# 002-main.net
KiCad netlist of a schematic drawn in EAGLE
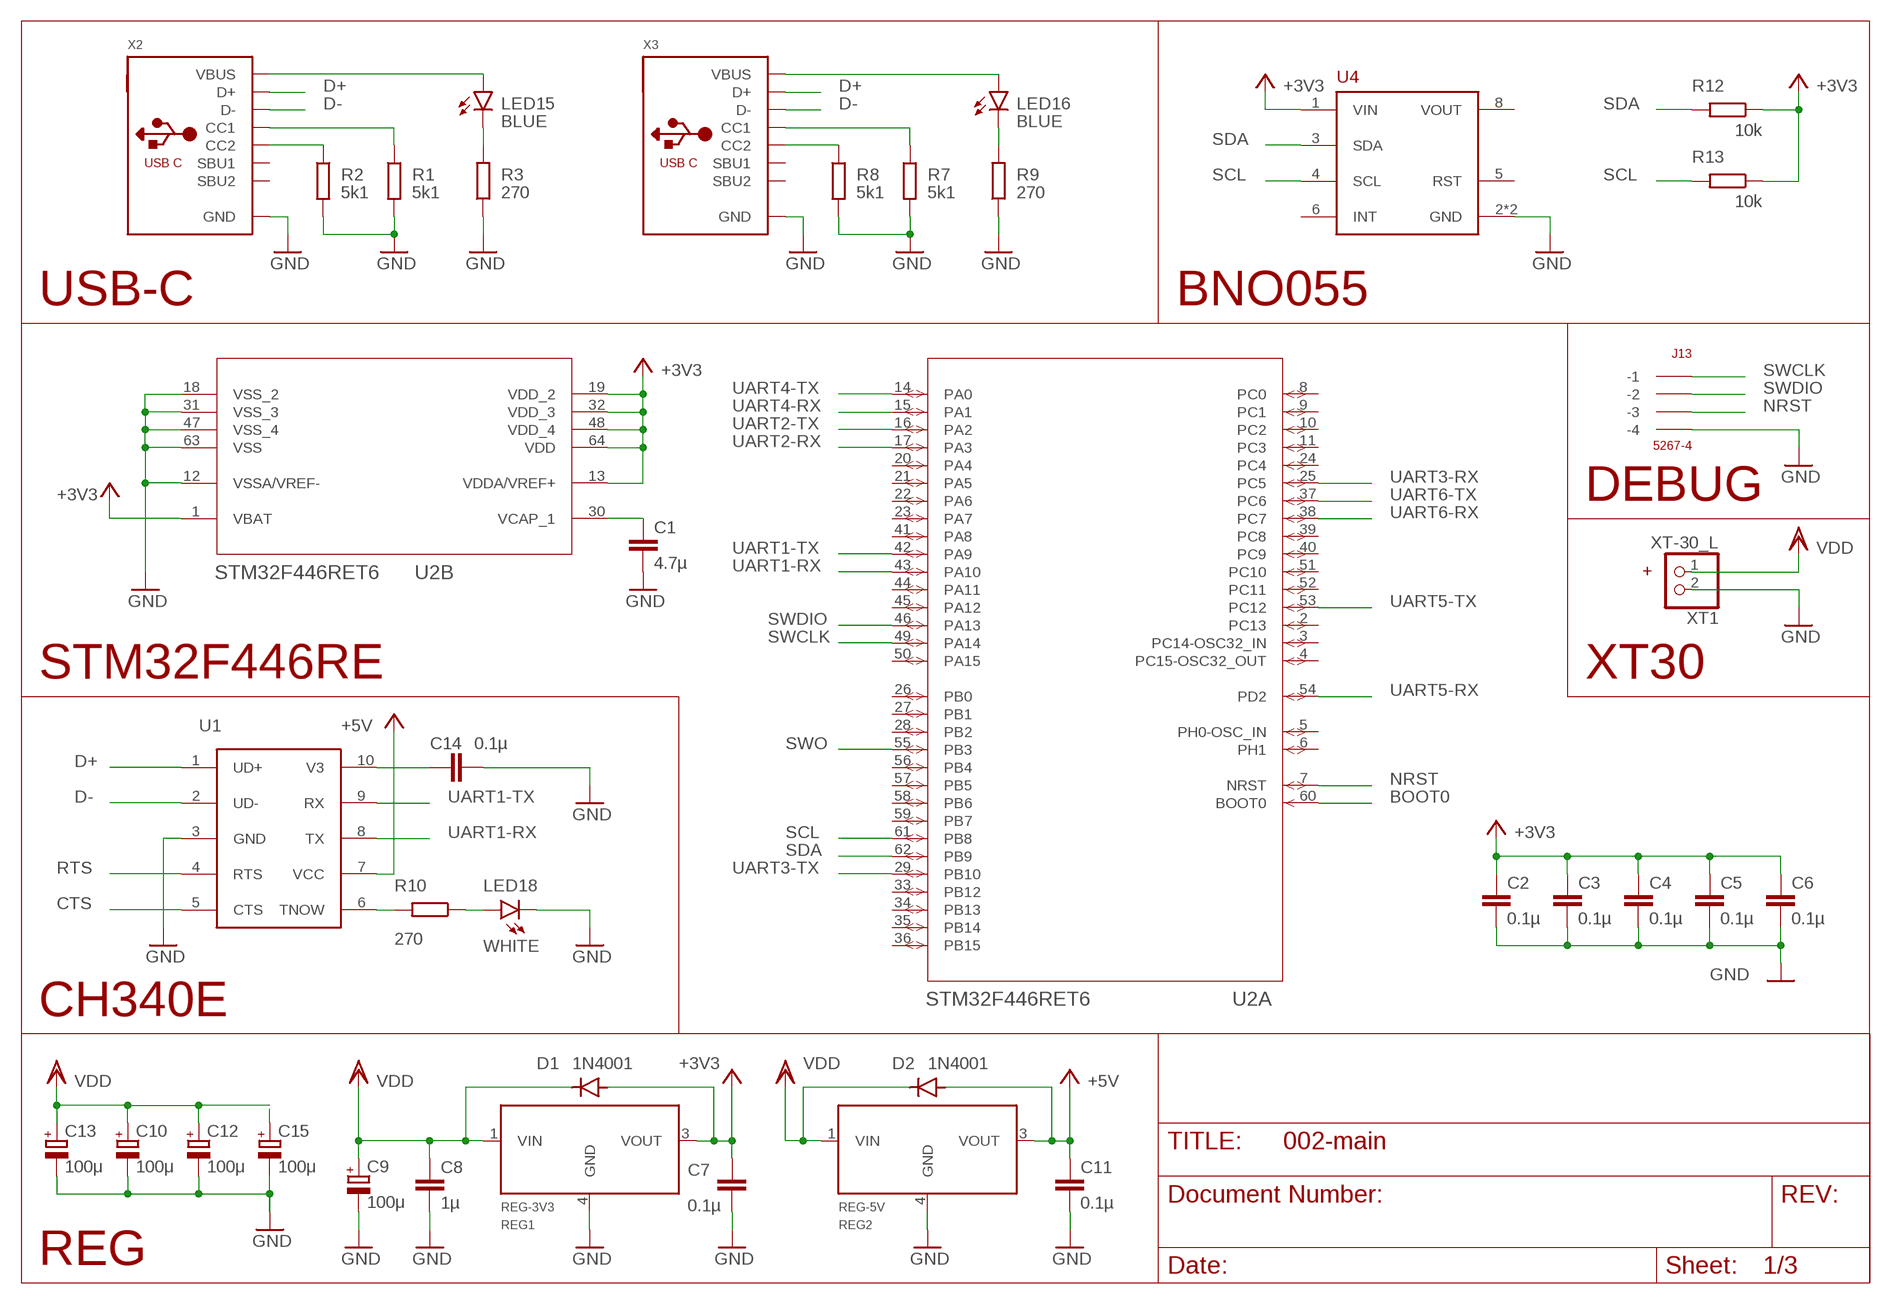
[diagram p0: schematic, sheet 1]
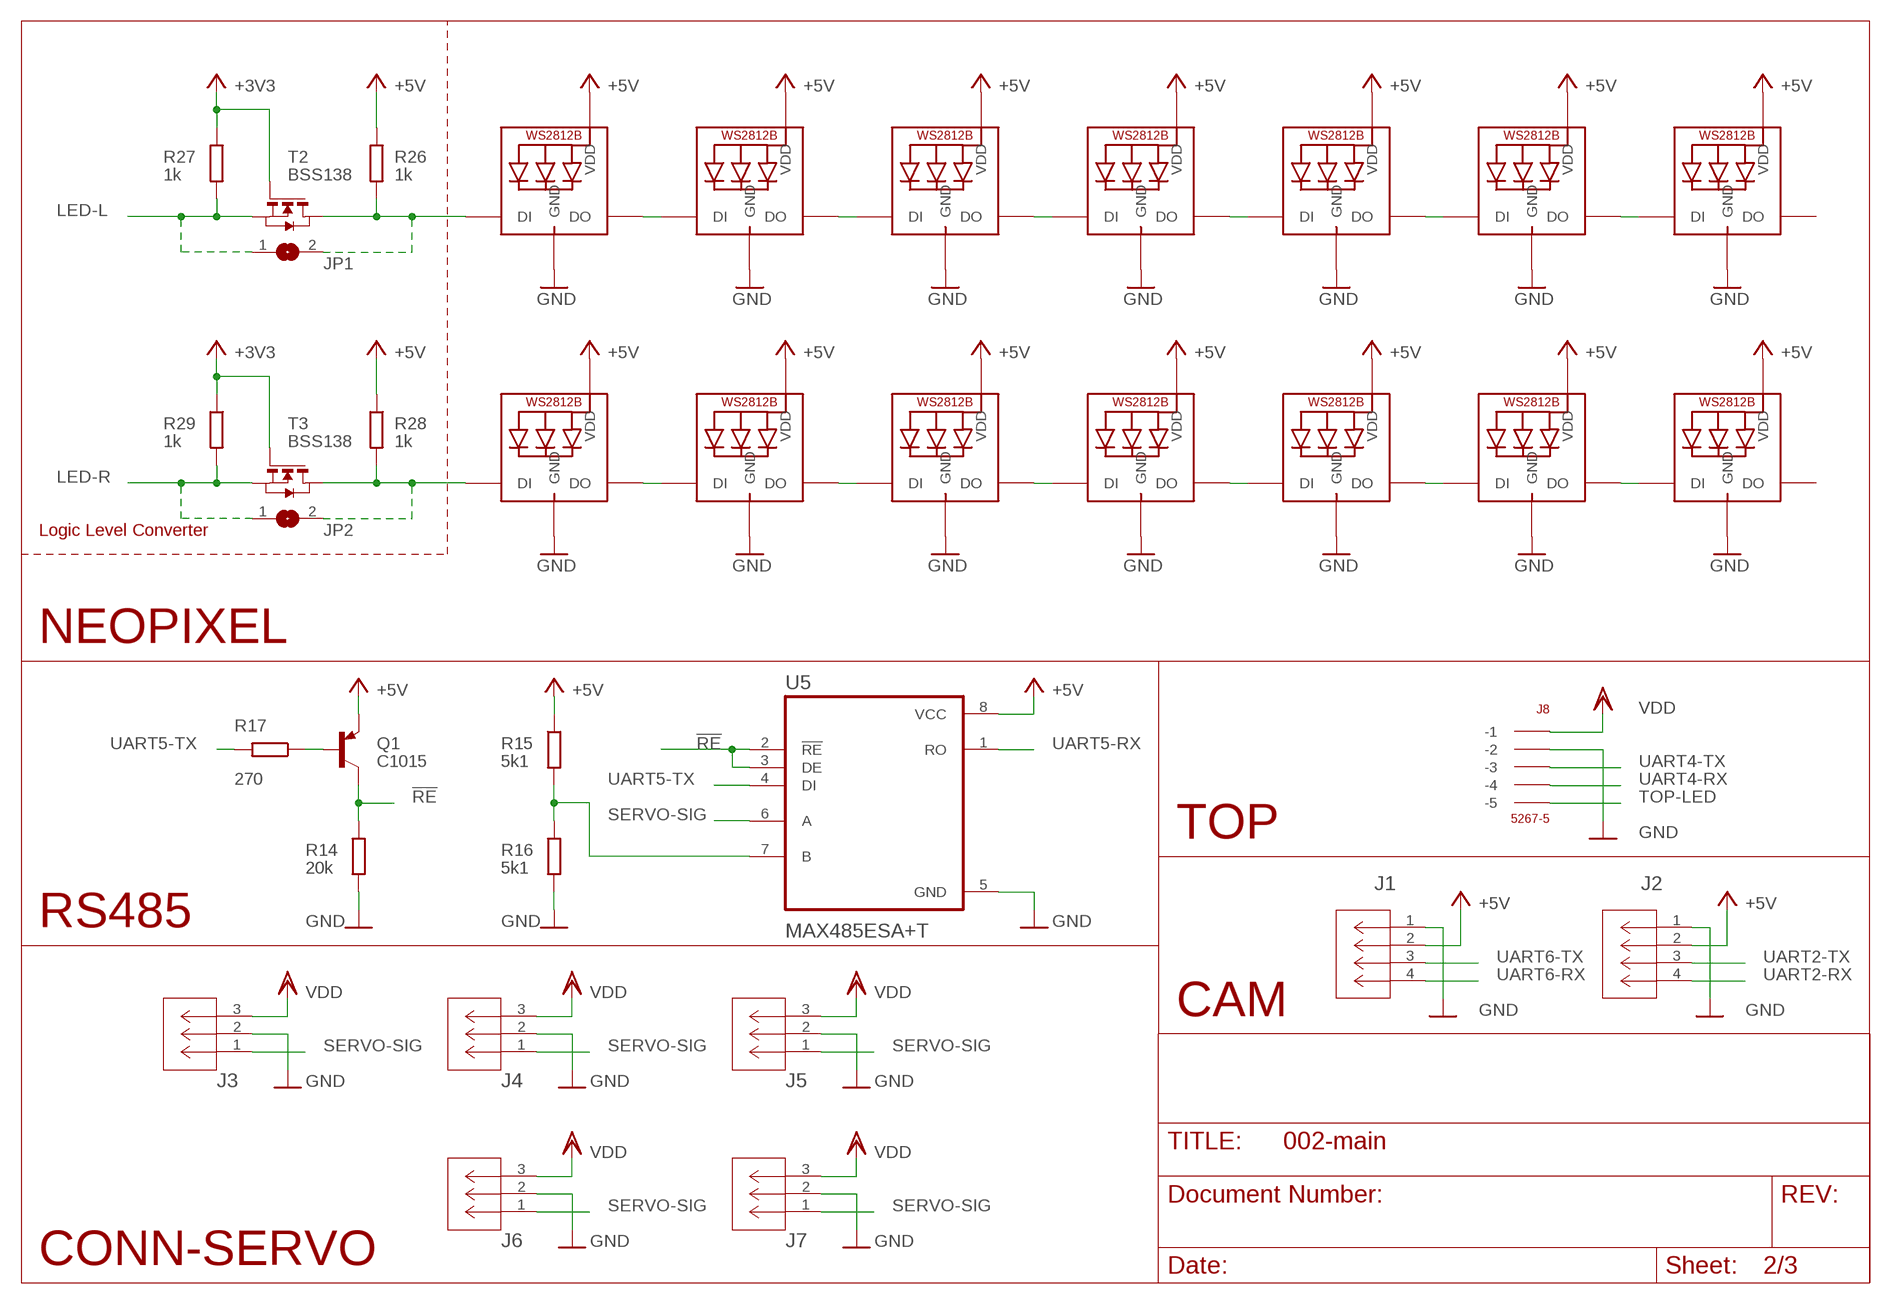
[diagram p1: schematic, sheet 2]
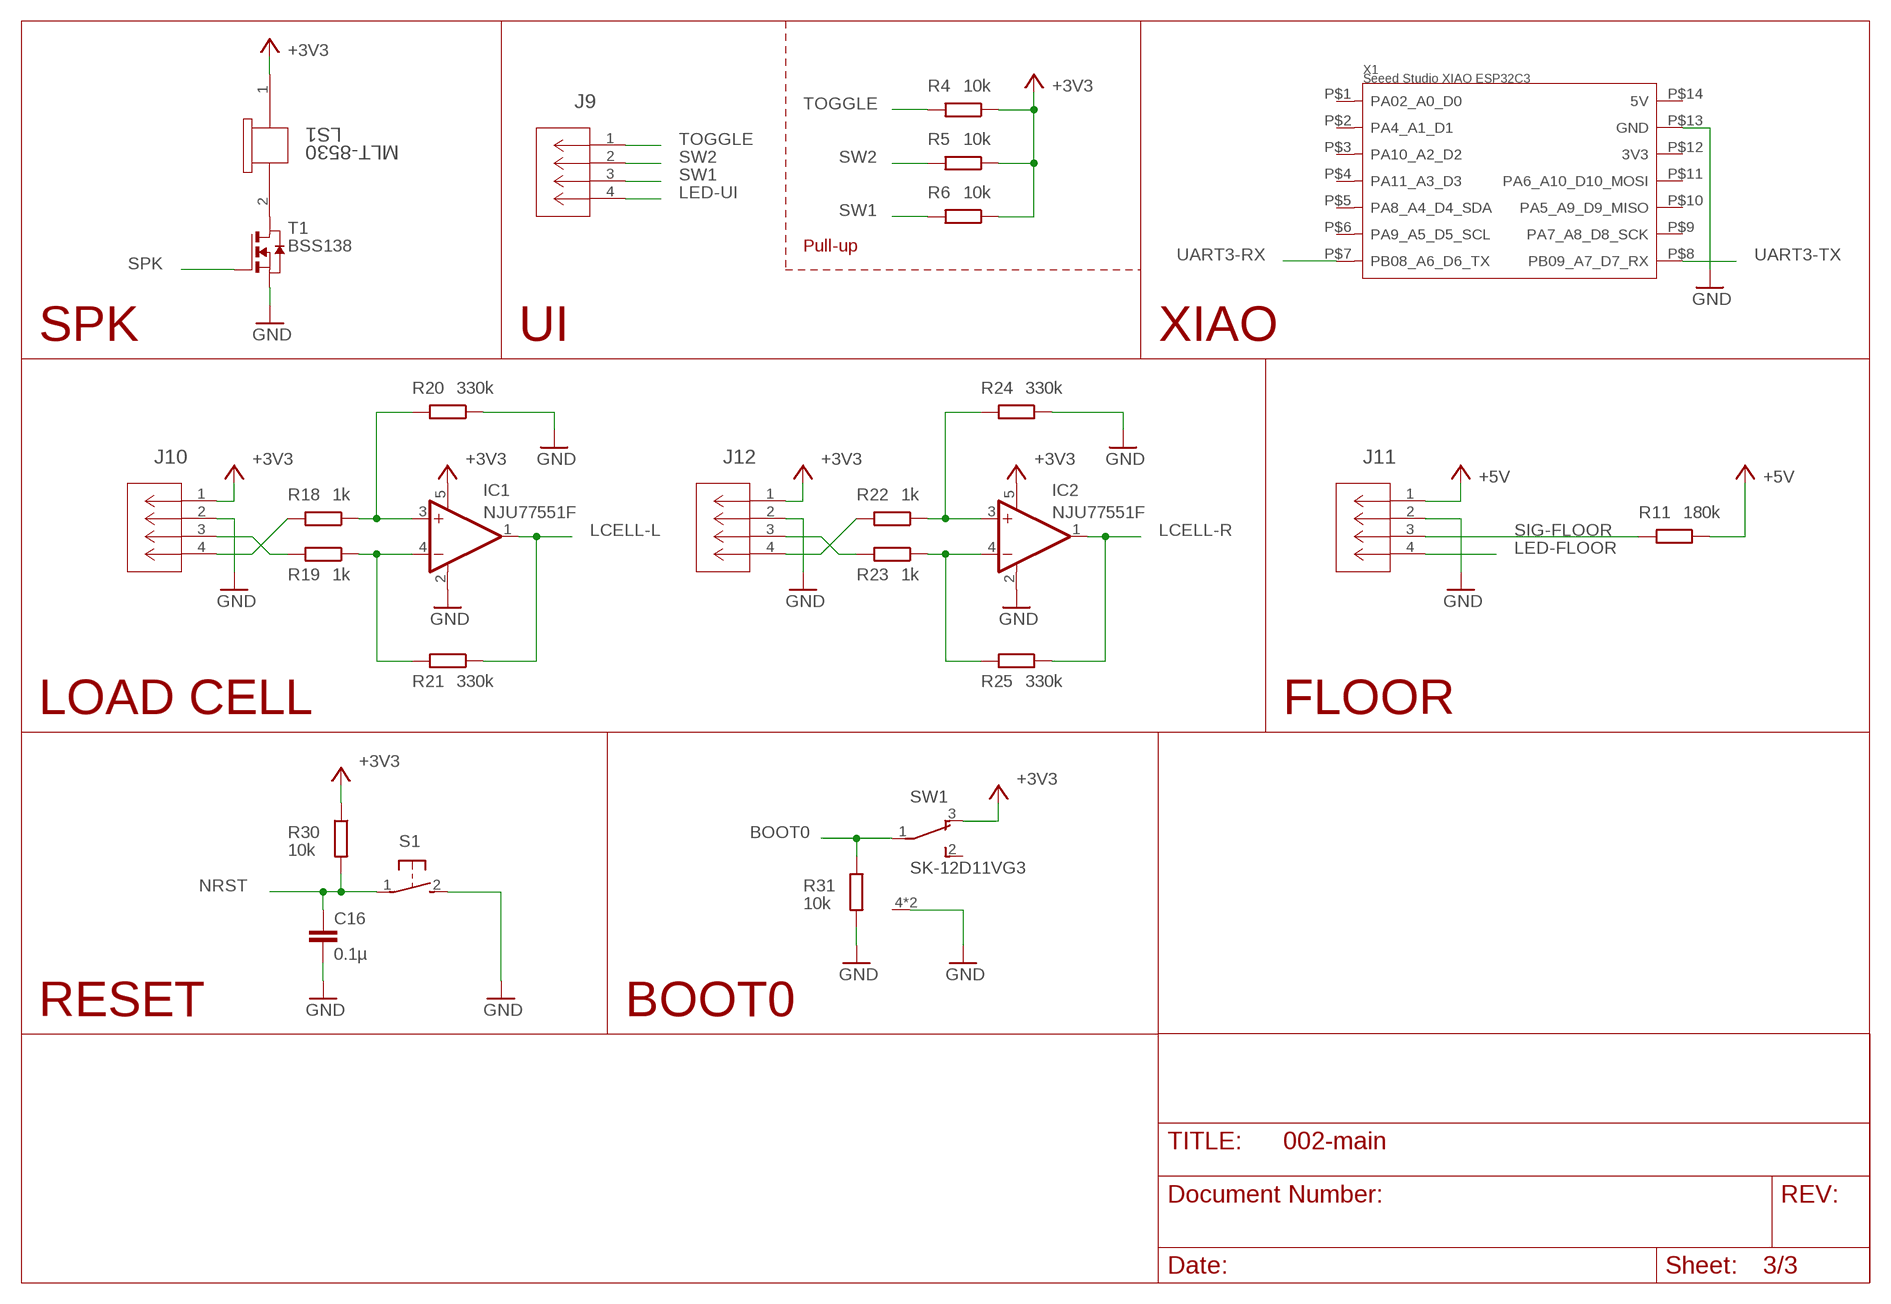
[diagram p2: schematic, sheet 3]

(export (version "E")
  (design (tool "Eeschema 10.0.6"))
  (components
    (comp (ref "C1")
      (value "4.7µ")
      (footprint "eagle-import:C0603")
      (libsource (lib "eagle-import") (part "C-EUC0603"))
    )
    (comp (ref "C2")
      (value "0.1µ")
      (footprint "eagle-import:C0603")
      (libsource (lib "eagle-import") (part "C-EUC0603"))
    )
    (comp (ref "C3")
      (value "0.1µ")
      (footprint "eagle-import:C0603")
      (libsource (lib "eagle-import") (part "C-EUC0603"))
    )
    (comp (ref "C4")
      (value "0.1µ")
      (footprint "eagle-import:C0603")
      (libsource (lib "eagle-import") (part "C-EUC0603"))
    )
    (comp (ref "C5")
      (value "0.1µ")
      (footprint "eagle-import:C0603")
      (libsource (lib "eagle-import") (part "C-EUC0603"))
    )
    (comp (ref "C6")
      (value "0.1µ")
      (footprint "eagle-import:C0603")
      (libsource (lib "eagle-import") (part "C-EUC0603"))
    )
    (comp (ref "C7")
      (value "0.1µ")
      (footprint "eagle-import:C0603")
      (libsource (lib "eagle-import") (part "C-EUC0603"))
    )
    (comp (ref "C8")
      (value "1µ")
      (footprint "eagle-import:C0603")
      (libsource (lib "eagle-import") (part "C-EUC0603"))
    )
    (comp (ref "C9")
      (value "100μ")
      (footprint "eagle-import:153CLV-0505")
      (libsource (lib "eagle-import") (part "CPOL-EU153CLV-0505"))
    )
    (comp (ref "C10")
      (value "100μ")
      (footprint "eagle-import:153CLV-0505")
      (libsource (lib "eagle-import") (part "CPOL-EU153CLV-0505"))
    )
    (comp (ref "C11")
      (value "0.1µ")
      (footprint "eagle-import:C0603")
      (libsource (lib "eagle-import") (part "C-EUC0603"))
    )
    (comp (ref "C12")
      (value "100μ")
      (footprint "eagle-import:153CLV-0505")
      (libsource (lib "eagle-import") (part "CPOL-EU153CLV-0505"))
    )
    (comp (ref "C13")
      (value "100μ")
      (footprint "eagle-import:153CLV-0505")
      (libsource (lib "eagle-import") (part "CPOL-EU153CLV-0505"))
    )
    (comp (ref "C14")
      (value "0.1µ")
      (footprint "eagle-import:C0603")
      (libsource (lib "eagle-import") (part "C-EUC0603"))
    )
    (comp (ref "C15")
      (value "100μ")
      (footprint "eagle-import:153CLV-0505")
      (libsource (lib "eagle-import") (part "CPOL-EU153CLV-0505"))
    )
    (comp (ref "D1")
      (value "1N4001")
      (footprint "eagle-import:SMA-DO214AC")
      (libsource (lib "eagle-import") (part "GF1"))
    )
    (comp (ref "D2")
      (value "1N4001")
      (footprint "eagle-import:SMA-DO214AC")
      (libsource (lib "eagle-import") (part "GF1"))
    )
    (comp (ref "J13")
      (value "5267-4")
      (footprint "eagle-import:5267-4")
      (libsource (lib "eagle-import") (part "5267-4"))
    )
    (comp (ref "LED15")
      (value "BLUE")
      (footprint "eagle-import:SML0603")
      (libsource (lib "eagle-import") (part "LEDSML0603"))
    )
    (comp (ref "LED16")
      (value "BLUE")
      (footprint "eagle-import:SML0603")
      (libsource (lib "eagle-import") (part "LEDSML0603"))
    )
    (comp (ref "LED18")
      (value "WHITE")
      (footprint "eagle-import:SML0603")
      (libsource (lib "eagle-import") (part "LEDSML0603"))
    )
    (comp (ref "R1")
      (value "5k1")
      (footprint "eagle-import:R0402")
      (libsource (lib "eagle-import") (part "R-EU_R0402"))
    )
    (comp (ref "R2")
      (value "5k1")
      (footprint "eagle-import:R0402")
      (libsource (lib "eagle-import") (part "R-EU_R0402"))
    )
    (comp (ref "R3")
      (value "270")
      (footprint "eagle-import:R0402")
      (libsource (lib "eagle-import") (part "R-EU_R0402"))
    )
    (comp (ref "R7")
      (value "5k1")
      (footprint "eagle-import:R0402")
      (libsource (lib "eagle-import") (part "R-EU_R0402"))
    )
    (comp (ref "R8")
      (value "5k1")
      (footprint "eagle-import:R0402")
      (libsource (lib "eagle-import") (part "R-EU_R0402"))
    )
    (comp (ref "R9")
      (value "270")
      (footprint "eagle-import:R0402")
      (libsource (lib "eagle-import") (part "R-EU_R0402"))
    )
    (comp (ref "R10")
      (value "270")
      (footprint "eagle-import:R0402")
      (libsource (lib "eagle-import") (part "R-EU_R0402"))
    )
    (comp (ref "R12")
      (value "10k")
      (footprint "eagle-import:R0402")
      (libsource (lib "eagle-import") (part "R-EU_R0402"))
    )
    (comp (ref "R13")
      (value "10k")
      (footprint "eagle-import:R0402")
      (libsource (lib "eagle-import") (part "R-EU_R0402"))
    )
    (comp (ref "REG1")
      (value "REG-3V3")
      (footprint "eagle-import:MYPARTS_D-PAK_TO252AA")
      (libsource (lib "eagle-import") (part "MYPARTS_NJM7800S-REGULATOR"))
    )
    (comp (ref "REG2")
      (value "REG-5V")
      (footprint "eagle-import:MYPARTS_D-PAK_TO252AA")
      (libsource (lib "eagle-import") (part "MYPARTS_NJM7800S-REGULATOR"))
    )
    (comp (ref "U1")
      (value "CH340ESMD")
      (footprint "eagle-import:MSOP10")
      (libsource (lib "eagle-import") (part "CH340ESMD"))
    )
    (comp (ref "U2")
      (value "STM32F446RET6")
      (footprint "eagle-import:LQFP64-10X10MM")
      (fields (field (name "COPYRIGHT") "Copyright (C) 2022 Ultra Librarian. All rights reserved."))
      (libsource (lib "eagle-import") (part "STM32F446RET6"))
    )
    (comp (ref "U4")
      (value "BNO055")
      (footprint "eagle-import:SOCKET-08")
      (libsource (lib "eagle-import") (part "BNO055"))
    )
    (comp (ref "X2")
      (value "USB_C")
      (footprint "eagle-import:USB_C_CUSB31-CFM2AX-01-X")
      (libsource (lib "eagle-import") (part "USB_C"))
    )
    (comp (ref "X3")
      (value "USB_C")
      (footprint "eagle-import:USB_C_CUSB31-CFM2AX-01-X")
      (libsource (lib "eagle-import") (part "USB_C"))
    )
    (comp (ref "XT1")
      (value "XT-30_L")
      (footprint "eagle-import:XT-30_L")
      (libsource (lib "eagle-import") (part "XT-30_L"))
    )
    (comp (ref "C16")
      (value "0.1µ")
      (footprint "eagle-import:C0603")
      (libsource (lib "eagle-import") (part "C-EUC0603"))
    )
    (comp (ref "IC1")
      (value "NJU77551F")
      (footprint "eagle-import:SOT23-5")
      (fields (field (name "MPN") "OPA340NA/3KG4"))
      (libsource (lib "eagle-import") (part "OPA340N"))
    )
    (comp (ref "IC2")
      (value "NJU77551F")
      (footprint "eagle-import:SOT23-5")
      (fields (field (name "MPN") "OPA340NA/3KG4"))
      (libsource (lib "eagle-import") (part "OPA340N"))
    )
    (comp (ref "J9")
      (value "22057045")
      (footprint "eagle-import:CON_22057045_MOL")
      (fields (field (name "COPYRIGHT") "Copyright (C) 2022 Ultra Librarian. All rights reserved."))
      (libsource (lib "eagle-import") (part "22057045"))
    )
    (comp (ref "J10")
      (value "22057045")
      (footprint "eagle-import:CON_22057045_MOL")
      (fields (field (name "COPYRIGHT") "Copyright (C) 2022 Ultra Librarian. All rights reserved."))
      (libsource (lib "eagle-import") (part "22057045"))
    )
    (comp (ref "J11")
      (value "22057045")
      (footprint "eagle-import:CON_22057045_MOL")
      (fields (field (name "COPYRIGHT") "Copyright (C) 2022 Ultra Librarian. All rights reserved."))
      (libsource (lib "eagle-import") (part "22057045"))
    )
    (comp (ref "J12")
      (value "22057045")
      (footprint "eagle-import:CON_22057045_MOL")
      (fields (field (name "COPYRIGHT") "Copyright (C) 2022 Ultra Librarian. All rights reserved."))
      (libsource (lib "eagle-import") (part "22057045"))
    )
    (comp (ref "LS1")
      (value "MLT-8530")
      (footprint "eagle-import:MLT-8530_JHE")
      (fields (field (name "COPYRIGHT") "Copyright (C) 2022 Ultra Librarian. All rights reserved."))
      (libsource (lib "eagle-import") (part "MLT-8530"))
    )
    (comp (ref "R4")
      (value "10k")
      (footprint "eagle-import:R0402")
      (libsource (lib "eagle-import") (part "R-EU_R0402"))
    )
    (comp (ref "R5")
      (value "10k")
      (footprint "eagle-import:R0402")
      (libsource (lib "eagle-import") (part "R-EU_R0402"))
    )
    (comp (ref "R6")
      (value "10k")
      (footprint "eagle-import:R0402")
      (libsource (lib "eagle-import") (part "R-EU_R0402"))
    )
    (comp (ref "R11")
      (value "180k")
      (footprint "eagle-import:R0402")
      (libsource (lib "eagle-import") (part "R-EU_R0402"))
    )
    (comp (ref "R18")
      (value "1k")
      (footprint "eagle-import:R0402")
      (libsource (lib "eagle-import") (part "R-EU_R0402"))
    )
    (comp (ref "R19")
      (value "1k")
      (footprint "eagle-import:R0402")
      (libsource (lib "eagle-import") (part "R-EU_R0402"))
    )
    (comp (ref "R20")
      (value "330k")
      (footprint "eagle-import:R0402")
      (libsource (lib "eagle-import") (part "R-EU_R0402"))
    )
    (comp (ref "R21")
      (value "330k")
      (footprint "eagle-import:R0402")
      (libsource (lib "eagle-import") (part "R-EU_R0402"))
    )
    (comp (ref "R22")
      (value "1k")
      (footprint "eagle-import:R0402")
      (libsource (lib "eagle-import") (part "R-EU_R0402"))
    )
    (comp (ref "R23")
      (value "1k")
      (footprint "eagle-import:R0402")
      (libsource (lib "eagle-import") (part "R-EU_R0402"))
    )
    (comp (ref "R24")
      (value "330k")
      (footprint "eagle-import:R0402")
      (libsource (lib "eagle-import") (part "R-EU_R0402"))
    )
    (comp (ref "R25")
      (value "330k")
      (footprint "eagle-import:R0402")
      (libsource (lib "eagle-import") (part "R-EU_R0402"))
    )
    (comp (ref "R30")
      (value "10k")
      (footprint "eagle-import:R0402")
      (libsource (lib "eagle-import") (part "R-EU_R0402"))
    )
    (comp (ref "R31")
      (value "10k")
      (footprint "eagle-import:R0402")
      (libsource (lib "eagle-import") (part "R-EU_R0402"))
    )
    (comp (ref "S1")
      (value "31-XX")
      (footprint "eagle-import:B3F-31XX")
      (fields (field (name "MPN") "B3F-3100"))
      (libsource (lib "eagle-import") (part "31-XX"))
    )
    (comp (ref "SW1")
      (value "SK-12D11VG3")
      (footprint "eagle-import:SK-12D11VG3")
      (libsource (lib "eagle-import") (part "SK-12D11VG3"))
    )
    (comp (ref "T1")
      (value "BSS138")
      (footprint "eagle-import:SOT-23")
      (libsource (lib "eagle-import") (part "NMOSSOT23"))
    )
    (comp (ref "X1")
      (value "Seeed Studio XIAO ESP32C3")
      (footprint "eagle-import:XIAO-PINHEAD")
      (libsource (lib "eagle-import") (part "SEEEDUINO-XIAO-DIP"))
    )
    (comp (ref "J1")
      (value "22057045")
      (footprint "eagle-import:CON_22057045_MOL")
      (fields (field (name "COPYRIGHT") "Copyright (C) 2022 Ultra Librarian. All rights reserved."))
      (libsource (lib "eagle-import") (part "22057045"))
    )
    (comp (ref "J2")
      (value "22057045")
      (footprint "eagle-import:CON_22057045_MOL")
      (fields (field (name "COPYRIGHT") "Copyright (C) 2022 Ultra Librarian. All rights reserved."))
      (libsource (lib "eagle-import") (part "22057045"))
    )
    (comp (ref "J3")
      (value "22057035")
      (footprint "eagle-import:CON_22057035_MOL")
      (fields (field (name "COPYRIGHT") "Copyright (C) 2022 Ultra Librarian. All rights reserved."))
      (libsource (lib "eagle-import") (part "22057035"))
    )
    (comp (ref "J4")
      (value "22057035")
      (footprint "eagle-import:CON_22057035_MOL")
      (fields (field (name "COPYRIGHT") "Copyright (C) 2022 Ultra Librarian. All rights reserved."))
      (libsource (lib "eagle-import") (part "22057035"))
    )
    (comp (ref "J5")
      (value "22057035")
      (footprint "eagle-import:CON_22057035_MOL")
      (fields (field (name "COPYRIGHT") "Copyright (C) 2022 Ultra Librarian. All rights reserved."))
      (libsource (lib "eagle-import") (part "22057035"))
    )
    (comp (ref "J6")
      (value "22057035")
      (footprint "eagle-import:CON_22057035_MOL")
      (fields (field (name "COPYRIGHT") "Copyright (C) 2022 Ultra Librarian. All rights reserved."))
      (libsource (lib "eagle-import") (part "22057035"))
    )
    (comp (ref "J7")
      (value "22057035")
      (footprint "eagle-import:CON_22057035_MOL")
      (fields (field (name "COPYRIGHT") "Copyright (C) 2022 Ultra Librarian. All rights reserved."))
      (libsource (lib "eagle-import") (part "22057035"))
    )
    (comp (ref "J8")
      (value "5267-5")
      (footprint "eagle-import:5267-5")
      (libsource (lib "eagle-import") (part "5267-5"))
    )
    (comp (ref "JP1")
      (value "JP2")
      (footprint "eagle-import:JP2")
      (libsource (lib "eagle-import") (part "JP2"))
    )
    (comp (ref "JP2")
      (value "JP2")
      (footprint "eagle-import:JP2")
      (libsource (lib "eagle-import") (part "JP2"))
    )
    (comp (ref "LED1")
      (value "WS2812B_2020")
      (footprint "eagle-import:WS2812B_2020")
      (libsource (lib "eagle-import") (part "WS2812B_2020"))
    )
    (comp (ref "LED2")
      (value "WS2812B_2020")
      (footprint "eagle-import:WS2812B_2020")
      (libsource (lib "eagle-import") (part "WS2812B_2020"))
    )
    (comp (ref "LED3")
      (value "WS2812B_2020")
      (footprint "eagle-import:WS2812B_2020")
      (libsource (lib "eagle-import") (part "WS2812B_2020"))
    )
    (comp (ref "LED4")
      (value "WS2812B_2020")
      (footprint "eagle-import:WS2812B_2020")
      (libsource (lib "eagle-import") (part "WS2812B_2020"))
    )
    (comp (ref "LED5")
      (value "WS2812B_2020")
      (footprint "eagle-import:WS2812B_2020")
      (libsource (lib "eagle-import") (part "WS2812B_2020"))
    )
    (comp (ref "LED6")
      (value "WS2812B_2020")
      (footprint "eagle-import:WS2812B_2020")
      (libsource (lib "eagle-import") (part "WS2812B_2020"))
    )
    (comp (ref "LED7")
      (value "WS2812B_2020")
      (footprint "eagle-import:WS2812B_2020")
      (libsource (lib "eagle-import") (part "WS2812B_2020"))
    )
    (comp (ref "LED8")
      (value "WS2812B_2020")
      (footprint "eagle-import:WS2812B_2020")
      (libsource (lib "eagle-import") (part "WS2812B_2020"))
    )
    (comp (ref "LED9")
      (value "WS2812B_2020")
      (footprint "eagle-import:WS2812B_2020")
      (libsource (lib "eagle-import") (part "WS2812B_2020"))
    )
    (comp (ref "LED10")
      (value "WS2812B_2020")
      (footprint "eagle-import:WS2812B_2020")
      (libsource (lib "eagle-import") (part "WS2812B_2020"))
    )
    (comp (ref "LED11")
      (value "WS2812B_2020")
      (footprint "eagle-import:WS2812B_2020")
      (libsource (lib "eagle-import") (part "WS2812B_2020"))
    )
    (comp (ref "LED12")
      (value "WS2812B_2020")
      (footprint "eagle-import:WS2812B_2020")
      (libsource (lib "eagle-import") (part "WS2812B_2020"))
    )
    (comp (ref "LED13")
      (value "WS2812B_2020")
      (footprint "eagle-import:WS2812B_2020")
      (libsource (lib "eagle-import") (part "WS2812B_2020"))
    )
    (comp (ref "LED14")
      (value "WS2812B_2020")
      (footprint "eagle-import:WS2812B_2020")
      (libsource (lib "eagle-import") (part "WS2812B_2020"))
    )
    (comp (ref "Q1")
      (value "C1015")
      (footprint "eagle-import:SOT23")
      (libsource (lib "eagle-import") (part "BCX71SMD"))
    )
    (comp (ref "R14")
      (value "20k")
      (footprint "eagle-import:R0402")
      (libsource (lib "eagle-import") (part "R-EU_R0402"))
    )
    (comp (ref "R15")
      (value "5k1")
      (footprint "eagle-import:R0402")
      (libsource (lib "eagle-import") (part "R-EU_R0402"))
    )
    (comp (ref "R16")
      (value "5k1")
      (footprint "eagle-import:R0402")
      (libsource (lib "eagle-import") (part "R-EU_R0402"))
    )
    (comp (ref "R17")
      (value "270")
      (footprint "eagle-import:R0402")
      (libsource (lib "eagle-import") (part "R-EU_R0402"))
    )
    (comp (ref "R26")
      (value "1k")
      (footprint "eagle-import:R0402")
      (libsource (lib "eagle-import") (part "R-EU_R0402"))
    )
    (comp (ref "R27")
      (value "1k")
      (footprint "eagle-import:R0402")
      (libsource (lib "eagle-import") (part "R-EU_R0402"))
    )
    (comp (ref "R28")
      (value "1k")
      (footprint "eagle-import:R0402")
      (libsource (lib "eagle-import") (part "R-EU_R0402"))
    )
    (comp (ref "R29")
      (value "1k")
      (footprint "eagle-import:R0402")
      (libsource (lib "eagle-import") (part "R-EU_R0402"))
    )
    (comp (ref "T2")
      (value "BSS138")
      (footprint "eagle-import:SOT-23")
      (libsource (lib "eagle-import") (part "NMOSSOT23"))
    )
    (comp (ref "T3")
      (value "BSS138")
      (footprint "eagle-import:SOT-23")
      (libsource (lib "eagle-import") (part "NMOSSOT23"))
    )
    (comp (ref "U5")
      (value "MAX485ESA+T")
      (footprint "eagle-import:SOIC127P600X175-8N")
      (fields (field (name "MF") "Maxim Integrated") (field (name "MP") "MAX485ESA"))
      (libsource (lib "eagle-import") (part "MAX485ESA+T"))
    )
  )
  (nets
    (net (code "1") (name "+3V3") (class "Default")
      (node (ref "C2") (pin "1") (pinfunction "1_1") (pintype "passive"))
      (node (ref "C3") (pin "1") (pinfunction "1_1") (pintype "passive"))
      (node (ref "C4") (pin "1") (pinfunction "1_1") (pintype "passive"))
      (node (ref "C5") (pin "1") (pinfunction "1_1") (pintype "passive"))
      (node (ref "C6") (pin "1") (pinfunction "1_1") (pintype "passive"))
      (node (ref "C7") (pin "1") (pinfunction "1_1") (pintype "passive"))
      (node (ref "D1") (pin "A") (pinfunction "A_A") (pintype "passive"))
      (node (ref "IC1") (pin "5") (pinfunction "V+_5") (pintype "power_in"))
      (node (ref "IC2") (pin "5") (pinfunction "V+_5") (pintype "power_in"))
      (node (ref "J10") (pin "1") (pinfunction "1_1") (pintype "passive"))
      (node (ref "J12") (pin "1") (pinfunction "1_1") (pintype "passive"))
      (node (ref "LS1") (pin "1") (pinfunction "1_1") (pintype "passive"))
      (node (ref "R12") (pin "1") (pinfunction "1_1") (pintype "passive"))
      (node (ref "R13") (pin "1") (pinfunction "1_1") (pintype "passive"))
      (node (ref "R27") (pin "1") (pinfunction "1_1") (pintype "passive"))
      (node (ref "R29") (pin "1") (pinfunction "1_1") (pintype "passive"))
      (node (ref "R30") (pin "1") (pinfunction "1_1") (pintype "passive"))
      (node (ref "R4") (pin "1") (pinfunction "1_1") (pintype "passive"))
      (node (ref "R5") (pin "1") (pinfunction "1_1") (pintype "passive"))
      (node (ref "R6") (pin "1") (pinfunction "1_1") (pintype "passive"))
      (node (ref "REG1") (pin "3") (pinfunction "VOUT_3") (pintype "passive"))
      (node (ref "SW1") (pin "3") (pinfunction "O_3") (pintype "passive"))
      (node (ref "T2") (pin "3") (pinfunction "G_3") (pintype "passive"))
      (node (ref "T3") (pin "3") (pinfunction "G_3") (pintype "passive"))
      (node (ref "U2") (pin "1") (pinfunction "VBAT_1") (pintype "power_in"))
      (node (ref "U2") (pin "13") (pinfunction "VDDA/VREF+_13") (pintype "power_in"))
      (node (ref "U2") (pin "19") (pinfunction "VDD_2_19") (pintype "power_in"))
      (node (ref "U2") (pin "32") (pinfunction "VDD_3_32") (pintype "power_in"))
      (node (ref "U2") (pin "48") (pinfunction "VDD_4_48") (pintype "power_in"))
      (node (ref "U2") (pin "64") (pinfunction "VDD_64") (pintype "power_in"))
      (node (ref "U4") (pin "1") (pinfunction "VIN_1") (pintype "power_in"))
    )
    (net (code "2") (name "+5V") (class "Default")
      (node (ref "C11") (pin "1") (pinfunction "1_1") (pintype "passive"))
      (node (ref "D2") (pin "A") (pinfunction "A_A") (pintype "passive"))
      (node (ref "J1") (pin "2") (pinfunction "2_2") (pintype "passive"))
      (node (ref "J11") (pin "1") (pinfunction "1_1") (pintype "passive"))
      (node (ref "J2") (pin "2") (pinfunction "2_2") (pintype "passive"))
      (node (ref "LED1") (pin "4") (pinfunction "VDD_4") (pintype "power_in"))
      (node (ref "LED10") (pin "4") (pinfunction "VDD_4") (pintype "power_in"))
      (node (ref "LED11") (pin "4") (pinfunction "VDD_4") (pintype "power_in"))
      (node (ref "LED12") (pin "4") (pinfunction "VDD_4") (pintype "power_in"))
      (node (ref "LED13") (pin "4") (pinfunction "VDD_4") (pintype "power_in"))
      (node (ref "LED14") (pin "4") (pinfunction "VDD_4") (pintype "power_in"))
      (node (ref "LED2") (pin "4") (pinfunction "VDD_4") (pintype "power_in"))
      (node (ref "LED3") (pin "4") (pinfunction "VDD_4") (pintype "power_in"))
      (node (ref "LED4") (pin "4") (pinfunction "VDD_4") (pintype "power_in"))
      (node (ref "LED5") (pin "4") (pinfunction "VDD_4") (pintype "power_in"))
      (node (ref "LED6") (pin "4") (pinfunction "VDD_4") (pintype "power_in"))
      (node (ref "LED7") (pin "4") (pinfunction "VDD_4") (pintype "power_in"))
      (node (ref "LED8") (pin "4") (pinfunction "VDD_4") (pintype "power_in"))
      (node (ref "LED9") (pin "4") (pinfunction "VDD_4") (pintype "power_in"))
      (node (ref "Q1") (pin "2") (pinfunction "E_2") (pintype "passive"))
      (node (ref "R11") (pin "1") (pinfunction "1_1") (pintype "passive"))
      (node (ref "R15") (pin "1") (pinfunction "1_1") (pintype "passive"))
      (node (ref "R26") (pin "1") (pinfunction "1_1") (pintype "passive"))
      (node (ref "R28") (pin "1") (pinfunction "1_1") (pintype "passive"))
      (node (ref "REG2") (pin "3") (pinfunction "VOUT_3") (pintype "passive"))
      (node (ref "U1") (pin "7") (pinfunction "VCC_7") (pintype "power_in"))
      (node (ref "U5") (pin "8") (pinfunction "VCC_8") (pintype "power_in"))
    )
    (net (code "3") (name "BOOT0") (class "Default")
      (node (ref "R31") (pin "1") (pinfunction "1_1") (pintype "passive"))
      (node (ref "SW1") (pin "1") (pinfunction "P_1") (pintype "passive"))
      (node (ref "U2") (pin "60") (pinfunction "BOOT0_60") (pintype "input"))
    )
    (net (code "4") (name "CTS") (class "Default")
      (node (ref "U1") (pin "5") (pinfunction "CTS_5") (pintype "input"))
    )
    (net (code "5") (name "D+") (class "Default")
      (node (ref "U1") (pin "1") (pinfunction "UD+_1") (pintype "bidirectional"))
      (node (ref "X2") (pin "A6") (pinfunction "D+_A6") (pintype "bidirectional"))
      (node (ref "X2") (pin "B6") (pinfunction "D+_B6") (pintype "bidirectional"))
      (node (ref "X3") (pin "A6") (pinfunction "D+_A6") (pintype "bidirectional"))
      (node (ref "X3") (pin "B6") (pinfunction "D+_B6") (pintype "bidirectional"))
    )
    (net (code "6") (name "D-") (class "Default")
      (node (ref "U1") (pin "2") (pinfunction "UD-_2") (pintype "bidirectional"))
      (node (ref "X2") (pin "A7") (pinfunction "D-_A7") (pintype "bidirectional"))
      (node (ref "X2") (pin "B7") (pinfunction "D-_B7") (pintype "bidirectional"))
      (node (ref "X3") (pin "A7") (pinfunction "D-_A7") (pintype "bidirectional"))
      (node (ref "X3") (pin "B7") (pinfunction "D-_B7") (pintype "bidirectional"))
    )
    (net (code "7") (name "GND") (class "Default")
      (node (ref "C1") (pin "2") (pinfunction "2_2") (pintype "passive"))
      (node (ref "C10") (pin "-") (pinfunction "-_-") (pintype "passive"))
      (node (ref "C11") (pin "2") (pinfunction "2_2") (pintype "passive"))
      (node (ref "C12") (pin "-") (pinfunction "-_-") (pintype "passive"))
      (node (ref "C13") (pin "-") (pinfunction "-_-") (pintype "passive"))
      (node (ref "C14") (pin "2") (pinfunction "2_2") (pintype "passive"))
      (node (ref "C15") (pin "-") (pinfunction "-_-") (pintype "passive"))
      (node (ref "C16") (pin "2") (pinfunction "2_2") (pintype "passive"))
      (node (ref "C2") (pin "2") (pinfunction "2_2") (pintype "passive"))
      (node (ref "C3") (pin "2") (pinfunction "2_2") (pintype "passive"))
      (node (ref "C4") (pin "2") (pinfunction "2_2") (pintype "passive"))
      (node (ref "C5") (pin "2") (pinfunction "2_2") (pintype "passive"))
      (node (ref "C6") (pin "2") (pinfunction "2_2") (pintype "passive"))
      (node (ref "C7") (pin "2") (pinfunction "2_2") (pintype "passive"))
      (node (ref "C8") (pin "2") (pinfunction "2_2") (pintype "passive"))
      (node (ref "C9") (pin "-") (pinfunction "-_-") (pintype "passive"))
      (node (ref "IC1") (pin "2") (pinfunction "V-_2") (pintype "power_in"))
      (node (ref "IC2") (pin "2") (pinfunction "V-_2") (pintype "power_in"))
      (node (ref "J1") (pin "1") (pinfunction "1_1") (pintype "passive"))
      (node (ref "J10") (pin "2") (pinfunction "2_2") (pintype "passive"))
      (node (ref "J11") (pin "2") (pinfunction "2_2") (pintype "passive"))
      (node (ref "J12") (pin "2") (pinfunction "2_2") (pintype "passive"))
      (node (ref "J13") (pin "P$4") (pinfunction "-4_P$4") (pintype "bidirectional"))
      (node (ref "J2") (pin "1") (pinfunction "1_1") (pintype "passive"))
      (node (ref "J3") (pin "2") (pinfunction "2_2") (pintype "passive"))
      (node (ref "J4") (pin "2") (pinfunction "2_2") (pintype "passive"))
      (node (ref "J5") (pin "2") (pinfunction "2_2") (pintype "passive"))
      (node (ref "J6") (pin "2") (pinfunction "2_2") (pintype "passive"))
      (node (ref "J7") (pin "2") (pinfunction "2_2") (pintype "passive"))
      (node (ref "J8") (pin "P$2") (pinfunction "-2_P$2") (pintype "bidirectional"))
      (node (ref "LED1") (pin "2") (pinfunction "GND_2") (pintype "power_in"))
      (node (ref "LED10") (pin "2") (pinfunction "GND_2") (pintype "power_in"))
      (node (ref "LED11") (pin "2") (pinfunction "GND_2") (pintype "power_in"))
      (node (ref "LED12") (pin "2") (pinfunction "GND_2") (pintype "power_in"))
      (node (ref "LED13") (pin "2") (pinfunction "GND_2") (pintype "power_in"))
      (node (ref "LED14") (pin "2") (pinfunction "GND_2") (pintype "power_in"))
      (node (ref "LED18") (pin "C") (pinfunction "C_C") (pintype "passive"))
      (node (ref "LED2") (pin "2") (pinfunction "GND_2") (pintype "power_in"))
      (node (ref "LED3") (pin "2") (pinfunction "GND_2") (pintype "power_in"))
      (node (ref "LED4") (pin "2") (pinfunction "GND_2") (pintype "power_in"))
      (node (ref "LED5") (pin "2") (pinfunction "GND_2") (pintype "power_in"))
      (node (ref "LED6") (pin "2") (pinfunction "GND_2") (pintype "power_in"))
      (node (ref "LED7") (pin "2") (pinfunction "GND_2") (pintype "power_in"))
      (node (ref "LED8") (pin "2") (pinfunction "GND_2") (pintype "power_in"))
      (node (ref "LED9") (pin "2") (pinfunction "GND_2") (pintype "power_in"))
      (node (ref "R1") (pin "2") (pinfunction "2_2") (pintype "passive"))
      (node (ref "R14") (pin "2") (pinfunction "2_2") (pintype "passive"))
      (node (ref "R16") (pin "2") (pinfunction "2_2") (pintype "passive"))
      (node (ref "R2") (pin "2") (pinfunction "2_2") (pintype "passive"))
      (node (ref "R20") (pin "1") (pinfunction "1_1") (pintype "passive"))
      (node (ref "R24") (pin "1") (pinfunction "1_1") (pintype "passive"))
      (node (ref "R3") (pin "1") (pinfunction "1_1") (pintype "passive"))
      (node (ref "R31") (pin "2") (pinfunction "2_2") (pintype "passive"))
      (node (ref "R7") (pin "2") (pinfunction "2_2") (pintype "passive"))
      (node (ref "R8") (pin "2") (pinfunction "2_2") (pintype "passive"))
      (node (ref "R9") (pin "1") (pinfunction "1_1") (pintype "passive"))
      (node (ref "REG1") (pin "4") (pinfunction "GND_4") (pintype "passive"))
      (node (ref "REG2") (pin "4") (pinfunction "GND_4") (pintype "passive"))
      (node (ref "S1") (pin "2") (pinfunction "S_2") (pintype "passive"))
      (node (ref "SW1") (pin "4") (pinfunction "CASE_4") (pintype "bidirectional"))
      (node (ref "SW1") (pin "5") (pinfunction "CASE_5") (pintype "bidirectional"))
      (node (ref "T1") (pin "2") (pinfunction "S_2") (pintype "passive"))
      (node (ref "U1") (pin "3") (pinfunction "GND_3") (pintype "power_in"))
      (node (ref "U2") (pin "12") (pinfunction "VSSA/VREF-_12") (pintype "power_in"))
      (node (ref "U2") (pin "18") (pinfunction "VSS_2_18") (pintype "power_in"))
      (node (ref "U2") (pin "31") (pinfunction "VSS_3_31") (pintype "power_in"))
      (node (ref "U2") (pin "47") (pinfunction "VSS_4_47") (pintype "power_in"))
      (node (ref "U2") (pin "63") (pinfunction "VSS_63") (pintype "power_in"))
      (node (ref "U4") (pin "2") (pinfunction "GND_2") (pintype "power_in"))
      (node (ref "U4") (pin "7") (pinfunction "GND_7") (pintype "power_in"))
      (node (ref "U5") (pin "5") (pinfunction "GND_5") (pintype "power_in"))
      (node (ref "X1") (pin "P$13") (pinfunction "GND_P$13") (pintype "bidirectional"))
      (node (ref "X2") (pin "A1B12") (pinfunction "GND_A1B12") (pintype "power_in"))
      (node (ref "X2") (pin "B1A12") (pinfunction "GND_B1A12") (pintype "power_in"))
      (node (ref "X3") (pin "A1B12") (pinfunction "GND_A1B12") (pintype "power_in"))
      (node (ref "X3") (pin "B1A12") (pinfunction "GND_B1A12") (pintype "power_in"))
      (node (ref "XT1") (pin "2") (pinfunction "2_2") (pintype "passive"))
    )
    (net (code "8") (name "LCELL-L") (class "Default")
      (node (ref "IC1") (pin "1") (pinfunction "OUT_1") (pintype "output"))
      (node (ref "R21") (pin "1") (pinfunction "1_1") (pintype "passive"))
    )
    (net (code "9") (name "LCELL-R") (class "Default")
      (node (ref "IC2") (pin "1") (pinfunction "OUT_1") (pintype "output"))
      (node (ref "R25") (pin "1") (pinfunction "1_1") (pintype "passive"))
    )
    (net (code "10") (name "LED-FLOOR") (class "Default")
      (node (ref "J11") (pin "4") (pinfunction "4_4") (pintype "passive"))
    )
    (net (code "11") (name "LED-L") (class "Default")
      (node (ref "JP1") (pin "1") (pinfunction "1_1") (pintype "passive"))
      (node (ref "R27") (pin "2") (pinfunction "2_2") (pintype "passive"))
      (node (ref "T2") (pin "2") (pinfunction "S_2") (pintype "passive"))
    )
    (net (code "12") (name "LED-R") (class "Default")
      (node (ref "JP2") (pin "1") (pinfunction "1_1") (pintype "passive"))
      (node (ref "R29") (pin "2") (pinfunction "2_2") (pintype "passive"))
      (node (ref "T3") (pin "2") (pinfunction "S_2") (pintype "passive"))
    )
    (net (code "13") (name "LED-UI") (class "Default")
      (node (ref "J9") (pin "4") (pinfunction "4_4") (pintype "passive"))
    )
    (net (code "14") (name "NRST") (class "Default")
      (node (ref "C16") (pin "1") (pinfunction "1_1") (pintype "passive"))
      (node (ref "J13") (pin "P$3") (pinfunction "-3_P$3") (pintype "bidirectional"))
      (node (ref "R30") (pin "2") (pinfunction "2_2") (pintype "passive"))
      (node (ref "S1") (pin "1") (pinfunction "P_1") (pintype "passive"))
      (node (ref "U2") (pin "7") (pinfunction "NRST_7") (pintype "bidirectional"))
    )
    (net (code "15") (name "Net-(IC1-+IN)") (class "Default")
      (node (ref "IC1") (pin "3") (pinfunction "+IN_3") (pintype "input"))
      (node (ref "R18") (pin "1") (pinfunction "1_1") (pintype "passive"))
      (node (ref "R20") (pin "2") (pinfunction "2_2") (pintype "passive"))
    )
    (net (code "16") (name "Net-(IC1--IN)") (class "Default")
      (node (ref "IC1") (pin "4") (pinfunction "-IN_4") (pintype "input"))
      (node (ref "R19") (pin "1") (pinfunction "1_1") (pintype "passive"))
      (node (ref "R21") (pin "2") (pinfunction "2_2") (pintype "passive"))
    )
    (net (code "17") (name "Net-(IC2-+IN)") (class "Default")
      (node (ref "IC2") (pin "3") (pinfunction "+IN_3") (pintype "input"))
      (node (ref "R22") (pin "1") (pinfunction "1_1") (pintype "passive"))
      (node (ref "R24") (pin "2") (pinfunction "2_2") (pintype "passive"))
    )
    (net (code "18") (name "Net-(IC2--IN)") (class "Default")
      (node (ref "IC2") (pin "4") (pinfunction "-IN_4") (pintype "input"))
      (node (ref "R23") (pin "1") (pinfunction "1_1") (pintype "passive"))
      (node (ref "R25") (pin "2") (pinfunction "2_2") (pintype "passive"))
    )
    (net (code "19") (name "Net-(J10-Pad3)") (class "Default")
      (node (ref "J10") (pin "3") (pinfunction "3_3") (pintype "passive"))
      (node (ref "R19") (pin "2") (pinfunction "2_2") (pintype "passive"))
    )
    (net (code "20") (name "Net-(J10-Pad4)") (class "Default")
      (node (ref "J10") (pin "4") (pinfunction "4_4") (pintype "passive"))
      (node (ref "R18") (pin "2") (pinfunction "2_2") (pintype "passive"))
    )
    (net (code "21") (name "Net-(J12-Pad3)") (class "Default")
      (node (ref "J12") (pin "3") (pinfunction "3_3") (pintype "passive"))
      (node (ref "R23") (pin "2") (pinfunction "2_2") (pintype "passive"))
    )
    (net (code "22") (name "Net-(J12-Pad4)") (class "Default")
      (node (ref "J12") (pin "4") (pinfunction "4_4") (pintype "passive"))
      (node (ref "R22") (pin "2") (pinfunction "2_2") (pintype "passive"))
    )
    (net (code "23") (name "Net-(LED1-DI)") (class "Default")
      (node (ref "JP1") (pin "2") (pinfunction "2_2") (pintype "passive"))
      (node (ref "LED1") (pin "3") (pinfunction "DI_3") (pintype "input"))
      (node (ref "R26") (pin "2") (pinfunction "2_2") (pintype "passive"))
      (node (ref "T2") (pin "1") (pinfunction "D_1") (pintype "passive"))
    )
    (net (code "24") (name "Net-(LED1-DO)") (class "Default")
      (node (ref "LED1") (pin "1") (pinfunction "DO_1") (pintype "output"))
      (node (ref "LED2") (pin "3") (pinfunction "DI_3") (pintype "input"))
    )
    (net (code "25") (name "Net-(LED2-DO)") (class "Default")
      (node (ref "LED2") (pin "1") (pinfunction "DO_1") (pintype "output"))
      (node (ref "LED3") (pin "3") (pinfunction "DI_3") (pintype "input"))
    )
    (net (code "26") (name "Net-(LED3-DO)") (class "Default")
      (node (ref "LED3") (pin "1") (pinfunction "DO_1") (pintype "output"))
      (node (ref "LED4") (pin "3") (pinfunction "DI_3") (pintype "input"))
    )
    (net (code "27") (name "Net-(LED4-DO)") (class "Default")
      (node (ref "LED4") (pin "1") (pinfunction "DO_1") (pintype "output"))
      (node (ref "LED5") (pin "3") (pinfunction "DI_3") (pintype "input"))
    )
    (net (code "28") (name "Net-(LED5-DO)") (class "Default")
      (node (ref "LED5") (pin "1") (pinfunction "DO_1") (pintype "output"))
      (node (ref "LED6") (pin "3") (pinfunction "DI_3") (pintype "input"))
    )
    (net (code "29") (name "Net-(LED6-DO)") (class "Default")
      (node (ref "LED6") (pin "1") (pinfunction "DO_1") (pintype "output"))
      (node (ref "LED7") (pin "3") (pinfunction "DI_3") (pintype "input"))
    )
    (net (code "30") (name "Net-(LED8-DI)") (class "Default")
      (node (ref "JP2") (pin "2") (pinfunction "2_2") (pintype "passive"))
      (node (ref "LED8") (pin "3") (pinfunction "DI_3") (pintype "input"))
      (node (ref "R28") (pin "2") (pinfunction "2_2") (pintype "passive"))
      (node (ref "T3") (pin "1") (pinfunction "D_1") (pintype "passive"))
    )
    (net (code "31") (name "Net-(LED8-DO)") (class "Default")
      (node (ref "LED8") (pin "1") (pinfunction "DO_1") (pintype "output"))
      (node (ref "LED9") (pin "3") (pinfunction "DI_3") (pintype "input"))
    )
    (net (code "32") (name "Net-(LED10-DI)") (class "Default")
      (node (ref "LED10") (pin "3") (pinfunction "DI_3") (pintype "input"))
      (node (ref "LED9") (pin "1") (pinfunction "DO_1") (pintype "output"))
    )
    (net (code "33") (name "Net-(LED10-DO)") (class "Default")
      (node (ref "LED10") (pin "1") (pinfunction "DO_1") (pintype "output"))
      (node (ref "LED11") (pin "3") (pinfunction "DI_3") (pintype "input"))
    )
    (net (code "34") (name "Net-(LED11-DO)") (class "Default")
      (node (ref "LED11") (pin "1") (pinfunction "DO_1") (pintype "output"))
      (node (ref "LED12") (pin "3") (pinfunction "DI_3") (pintype "input"))
    )
    (net (code "35") (name "Net-(LED12-DO)") (class "Default")
      (node (ref "LED12") (pin "1") (pinfunction "DO_1") (pintype "output"))
      (node (ref "LED13") (pin "3") (pinfunction "DI_3") (pintype "input"))
    )
    (net (code "36") (name "Net-(LED13-DO)") (class "Default")
      (node (ref "LED13") (pin "1") (pinfunction "DO_1") (pintype "output"))
      (node (ref "LED14") (pin "3") (pinfunction "DI_3") (pintype "input"))
    )
    (net (code "37") (name "Net-(LED15-PadA)") (class "Default")
      (node (ref "LED15") (pin "A") (pinfunction "A_A") (pintype "passive"))
      (node (ref "X2") (pin "A4B9") (pinfunction "VBUS_A4B9") (pintype "power_in"))
      (node (ref "X2") (pin "B4A9") (pinfunction "VBUS_B4A9") (pintype "power_in"))
    )
    (net (code "38") (name "Net-(LED15-PadC)") (class "Default")
      (node (ref "LED15") (pin "C") (pinfunction "C_C") (pintype "passive"))
      (node (ref "R3") (pin "2") (pinfunction "2_2") (pintype "passive"))
    )
    (net (code "39") (name "Net-(LED16-PadA)") (class "Default")
      (node (ref "LED16") (pin "A") (pinfunction "A_A") (pintype "passive"))
      (node (ref "X3") (pin "A4B9") (pinfunction "VBUS_A4B9") (pintype "power_in"))
      (node (ref "X3") (pin "B4A9") (pinfunction "VBUS_B4A9") (pintype "power_in"))
    )
    (net (code "40") (name "Net-(LED16-PadC)") (class "Default")
      (node (ref "LED16") (pin "C") (pinfunction "C_C") (pintype "passive"))
      (node (ref "R9") (pin "2") (pinfunction "2_2") (pintype "passive"))
    )
    (net (code "41") (name "Net-(LED18-PadA)") (class "Default")
      (node (ref "LED18") (pin "A") (pinfunction "A_A") (pintype "passive"))
      (node (ref "R10") (pin "1") (pinfunction "1_1") (pintype "passive"))
    )
    (net (code "42") (name "Net-(Q1-B)") (class "Default")
      (node (ref "Q1") (pin "1") (pinfunction "B_1") (pintype "passive"))
      (node (ref "R17") (pin "1") (pinfunction "1_1") (pintype "passive"))
    )
    (net (code "43") (name "Net-(T1-D)") (class "Default")
      (node (ref "LS1") (pin "2") (pinfunction "2_2") (pintype "passive"))
      (node (ref "T1") (pin "1") (pinfunction "D_1") (pintype "passive"))
    )
    (net (code "44") (name "Net-(U1-TNOW)") (class "Default")
      (node (ref "R10") (pin "2") (pinfunction "2_2") (pintype "passive"))
      (node (ref "U1") (pin "6") (pinfunction "TNOW_6") (pintype "output"))
    )
    (net (code "45") (name "Net-(U1-V3)") (class "Default")
      (node (ref "C14") (pin "1") (pinfunction "1_1") (pintype "passive"))
      (node (ref "U1") (pin "10") (pinfunction "V3_10") (pintype "power_in"))
    )
    (net (code "46") (name "Net-(U2B-VCAP_1)") (class "Default")
      (node (ref "C1") (pin "1") (pinfunction "1_1") (pintype "passive"))
      (node (ref "U2") (pin "30") (pinfunction "VCAP_1_30") (pintype "power_in"))
    )
    (net (code "47") (name "Net-(U5-B)") (class "Default")
      (node (ref "R15") (pin "2") (pinfunction "2_2") (pintype "passive"))
      (node (ref "R16") (pin "1") (pinfunction "1_1") (pintype "passive"))
      (node (ref "U5") (pin "7") (pinfunction "B_7") (pintype "bidirectional"))
    )
    (net (code "48") (name "Net-(X2-CC1)") (class "Default")
      (node (ref "R1") (pin "1") (pinfunction "1_1") (pintype "passive"))
      (node (ref "X2") (pin "A5") (pinfunction "CC1_A5") (pintype "bidirectional"))
    )
    (net (code "49") (name "Net-(X2-CC2)") (class "Default")
      (node (ref "R2") (pin "1") (pinfunction "1_1") (pintype "passive"))
      (node (ref "X2") (pin "B5") (pinfunction "CC2_B5") (pintype "bidirectional"))
    )
    (net (code "50") (name "Net-(X3-CC1)") (class "Default")
      (node (ref "R7") (pin "1") (pinfunction "1_1") (pintype "passive"))
      (node (ref "X3") (pin "A5") (pinfunction "CC1_A5") (pintype "bidirectional"))
    )
    (net (code "51") (name "Net-(X3-CC2)") (class "Default")
      (node (ref "R8") (pin "1") (pinfunction "1_1") (pintype "passive"))
      (node (ref "X3") (pin "B5") (pinfunction "CC2_B5") (pintype "bidirectional"))
    )
    (net (code "52") (name "RTS") (class "Default")
      (node (ref "U1") (pin "4") (pinfunction "RTS_4") (pintype "output"))
    )
    (net (code "53") (name "SCL") (class "Default")
      (node (ref "R13") (pin "2") (pinfunction "2_2") (pintype "passive"))
      (node (ref "U2") (pin "61") (pinfunction "PB8_61") (pintype "bidirectional"))
      (node (ref "U4") (pin "4") (pinfunction "SCL_4") (pintype "bidirectional"))
    )
    (net (code "54") (name "SDA") (class "Default")
      (node (ref "R12") (pin "2") (pinfunction "2_2") (pintype "passive"))
      (node (ref "U2") (pin "62") (pinfunction "PB9_62") (pintype "bidirectional"))
      (node (ref "U4") (pin "3") (pinfunction "SDA_3") (pintype "bidirectional"))
    )
    (net (code "55") (name "SERVO-SIG") (class "Default")
      (node (ref "J3") (pin "1") (pinfunction "1_1") (pintype "passive"))
      (node (ref "J4") (pin "1") (pinfunction "1_1") (pintype "passive"))
      (node (ref "J5") (pin "1") (pinfunction "1_1") (pintype "passive"))
      (node (ref "J6") (pin "1") (pinfunction "1_1") (pintype "passive"))
      (node (ref "J7") (pin "1") (pinfunction "1_1") (pintype "passive"))
      (node (ref "U5") (pin "6") (pinfunction "A_6") (pintype "bidirectional"))
    )
    (net (code "56") (name "SIG-FLOOR") (class "Default")
      (node (ref "J11") (pin "3") (pinfunction "3_3") (pintype "passive"))
      (node (ref "R11") (pin "2") (pinfunction "2_2") (pintype "passive"))
    )
    (net (code "57") (name "SPK") (class "Default")
      (node (ref "T1") (pin "3") (pinfunction "G_3") (pintype "passive"))
    )
    (net (code "58") (name "SW1") (class "Default")
      (node (ref "J9") (pin "3") (pinfunction "3_3") (pintype "passive"))
      (node (ref "R6") (pin "2") (pinfunction "2_2") (pintype "passive"))
    )
    (net (code "59") (name "SW2") (class "Default")
      (node (ref "J9") (pin "2") (pinfunction "2_2") (pintype "passive"))
      (node (ref "R5") (pin "2") (pinfunction "2_2") (pintype "passive"))
    )
    (net (code "60") (name "SWCLK") (class "Default")
      (node (ref "J13") (pin "P$1") (pinfunction "-1_P$1") (pintype "bidirectional"))
      (node (ref "U2") (pin "49") (pinfunction "PA14_49") (pintype "bidirectional"))
    )
    (net (code "61") (name "SWDIO") (class "Default")
      (node (ref "J13") (pin "P$2") (pinfunction "-2_P$2") (pintype "bidirectional"))
      (node (ref "U2") (pin "46") (pinfunction "PA13_46") (pintype "bidirectional"))
    )
    (net (code "62") (name "SWO") (class "Default")
      (node (ref "U2") (pin "55") (pinfunction "PB3_55") (pintype "bidirectional"))
    )
    (net (code "63") (name "TOGGLE") (class "Default")
      (node (ref "J9") (pin "1") (pinfunction "1_1") (pintype "passive"))
      (node (ref "R4") (pin "2") (pinfunction "2_2") (pintype "passive"))
    )
    (net (code "64") (name "TOP-LED") (class "Default")
      (node (ref "J8") (pin "P$5") (pinfunction "-5_P$5") (pintype "bidirectional"))
    )
    (net (code "65") (name "UART1-RX") (class "Default")
      (node (ref "U1") (pin "8") (pinfunction "TX_8") (pintype "output"))
      (node (ref "U2") (pin "43") (pinfunction "PA10_43") (pintype "bidirectional"))
    )
    (net (code "66") (name "UART1-TX") (class "Default")
      (node (ref "U1") (pin "9") (pinfunction "RX_9") (pintype "input"))
      (node (ref "U2") (pin "42") (pinfunction "PA9_42") (pintype "bidirectional"))
    )
    (net (code "67") (name "UART2-RX") (class "Default")
      (node (ref "J2") (pin "4") (pinfunction "4_4") (pintype "passive"))
      (node (ref "U2") (pin "17") (pinfunction "PA3_17") (pintype "bidirectional"))
    )
    (net (code "68") (name "UART2-TX") (class "Default")
      (node (ref "J2") (pin "3") (pinfunction "3_3") (pintype "passive"))
      (node (ref "U2") (pin "16") (pinfunction "PA2_16") (pintype "bidirectional"))
    )
    (net (code "69") (name "UART3-RX") (class "Default")
      (node (ref "U2") (pin "25") (pinfunction "PC5_25") (pintype "bidirectional"))
      (node (ref "X1") (pin "P$7") (pinfunction "PB08_A6_D6_TX_P$7") (pintype "bidirectional"))
    )
    (net (code "70") (name "UART3-TX") (class "Default")
      (node (ref "U2") (pin "29") (pinfunction "PB10_29") (pintype "bidirectional"))
      (node (ref "X1") (pin "P$8") (pinfunction "PB09_A7_D7_RX_P$8") (pintype "bidirectional"))
    )
    (net (code "71") (name "UART4-RX") (class "Default")
      (node (ref "J8") (pin "P$4") (pinfunction "-4_P$4") (pintype "bidirectional"))
      (node (ref "U2") (pin "15") (pinfunction "PA1_15") (pintype "bidirectional"))
    )
    (net (code "72") (name "UART4-TX") (class "Default")
      (node (ref "J8") (pin "P$3") (pinfunction "-3_P$3") (pintype "bidirectional"))
      (node (ref "U2") (pin "14") (pinfunction "PA0_14") (pintype "bidirectional"))
    )
    (net (code "73") (name "UART5-RX") (class "Default")
      (node (ref "U2") (pin "54") (pinfunction "PD2_54") (pintype "bidirectional"))
      (node (ref "U5") (pin "1") (pinfunction "RO_1") (pintype "output"))
    )
    (net (code "74") (name "UART5-TX") (class "Default")
      (node (ref "R17") (pin "2") (pinfunction "2_2") (pintype "passive"))
      (node (ref "U2") (pin "53") (pinfunction "PC12_53") (pintype "bidirectional"))
      (node (ref "U5") (pin "4") (pinfunction "DI_4") (pintype "input"))
    )
    (net (code "75") (name "UART6-RX") (class "Default")
      (node (ref "J1") (pin "4") (pinfunction "4_4") (pintype "passive"))
      (node (ref "U2") (pin "38") (pinfunction "PC7_38") (pintype "bidirectional"))
    )
    (net (code "76") (name "UART6-TX") (class "Default")
      (node (ref "J1") (pin "3") (pinfunction "3_3") (pintype "passive"))
      (node (ref "U2") (pin "37") (pinfunction "PC6_37") (pintype "bidirectional"))
    )
    (net (code "77") (name "VDD") (class "Default")
      (node (ref "C10") (pin "+") (pinfunction "+_+") (pintype "passive"))
      (node (ref "C12") (pin "+") (pinfunction "+_+") (pintype "passive"))
      (node (ref "C13") (pin "+") (pinfunction "+_+") (pintype "passive"))
      (node (ref "C15") (pin "+") (pinfunction "+_+") (pintype "passive"))
      (node (ref "C8") (pin "1") (pinfunction "1_1") (pintype "passive"))
      (node (ref "C9") (pin "+") (pinfunction "+_+") (pintype "passive"))
      (node (ref "D1") (pin "K") (pinfunction "C_K") (pintype "passive"))
      (node (ref "D2") (pin "K") (pinfunction "C_K") (pintype "passive"))
      (node (ref "J3") (pin "3") (pinfunction "3_3") (pintype "passive"))
      (node (ref "J4") (pin "3") (pinfunction "3_3") (pintype "passive"))
      (node (ref "J5") (pin "3") (pinfunction "3_3") (pintype "passive"))
      (node (ref "J6") (pin "3") (pinfunction "3_3") (pintype "passive"))
      (node (ref "J7") (pin "3") (pinfunction "3_3") (pintype "passive"))
      (node (ref "J8") (pin "P$1") (pinfunction "-1_P$1") (pintype "bidirectional"))
      (node (ref "REG1") (pin "1") (pinfunction "VIN_1") (pintype "passive"))
      (node (ref "REG2") (pin "1") (pinfunction "VIN_1") (pintype "passive"))
      (node (ref "XT1") (pin "1") (pinfunction "1_1") (pintype "passive"))
    )
    (net (code "78") (name "VOUT") (class "Default")
      (node (ref "U4") (pin "8") (pinfunction "VOUT_8") (pintype "power_in"))
    )
    (net (code "79") (name "unconnected-(LED7-DO-Pad1)") (class "Default")
      (node (ref "LED7") (pin "1") (pinfunction "DO_1") (pintype "output"))
    )
    (net (code "80") (name "unconnected-(LED14-DO-Pad1)") (class "Default")
      (node (ref "LED14") (pin "1") (pinfunction "DO_1") (pintype "output"))
    )
    (net (code "81") (name "unconnected-(SW1-S-Pad2)") (class "Default")
      (node (ref "SW1") (pin "2") (pinfunction "S_2") (pintype "passive"))
    )
    (net (code "82") (name "unconnected-(U2A-PA4-Pad20)") (class "Default")
      (node (ref "U2") (pin "20") (pinfunction "PA4_20") (pintype "bidirectional"))
    )
    (net (code "83") (name "unconnected-(U2A-PA5-Pad21)") (class "Default")
      (node (ref "U2") (pin "21") (pinfunction "PA5_21") (pintype "bidirectional"))
    )
    (net (code "84") (name "unconnected-(U2A-PA6-Pad22)") (class "Default")
      (node (ref "U2") (pin "22") (pinfunction "PA6_22") (pintype "bidirectional"))
    )
    (net (code "85") (name "unconnected-(U2A-PA7-Pad23)") (class "Default")
      (node (ref "U2") (pin "23") (pinfunction "PA7_23") (pintype "bidirectional"))
    )
    (net (code "86") (name "unconnected-(U2A-PA8-Pad41)") (class "Default")
      (node (ref "U2") (pin "41") (pinfunction "PA8_41") (pintype "bidirectional"))
    )
    (net (code "87") (name "unconnected-(U2A-PA11-Pad44)") (class "Default")
      (node (ref "U2") (pin "44") (pinfunction "PA11_44") (pintype "bidirectional"))
    )
    (net (code "88") (name "unconnected-(U2A-PA12-Pad45)") (class "Default")
      (node (ref "U2") (pin "45") (pinfunction "PA12_45") (pintype "bidirectional"))
    )
    (net (code "89") (name "unconnected-(U2A-PA15-Pad50)") (class "Default")
      (node (ref "U2") (pin "50") (pinfunction "PA15_50") (pintype "bidirectional"))
    )
    (net (code "90") (name "unconnected-(U2A-PB0-Pad26)") (class "Default")
      (node (ref "U2") (pin "26") (pinfunction "PB0_26") (pintype "bidirectional"))
    )
    (net (code "91") (name "unconnected-(U2A-PB1-Pad27)") (class "Default")
      (node (ref "U2") (pin "27") (pinfunction "PB1_27") (pintype "bidirectional"))
    )
    (net (code "92") (name "unconnected-(U2A-PB2-Pad28)") (class "Default")
      (node (ref "U2") (pin "28") (pinfunction "PB2_28") (pintype "bidirectional"))
    )
    (net (code "93") (name "unconnected-(U2A-PB4-Pad56)") (class "Default")
      (node (ref "U2") (pin "56") (pinfunction "PB4_56") (pintype "bidirectional"))
    )
    (net (code "94") (name "unconnected-(U2A-PB5-Pad57)") (class "Default")
      (node (ref "U2") (pin "57") (pinfunction "PB5_57") (pintype "bidirectional"))
    )
    (net (code "95") (name "unconnected-(U2A-PB6-Pad58)") (class "Default")
      (node (ref "U2") (pin "58") (pinfunction "PB6_58") (pintype "bidirectional"))
    )
    (net (code "96") (name "unconnected-(U2A-PB7-Pad59)") (class "Default")
      (node (ref "U2") (pin "59") (pinfunction "PB7_59") (pintype "bidirectional"))
    )
    (net (code "97") (name "unconnected-(U2A-PB12-Pad33)") (class "Default")
      (node (ref "U2") (pin "33") (pinfunction "PB12_33") (pintype "bidirectional"))
    )
    (net (code "98") (name "unconnected-(U2A-PB13-Pad34)") (class "Default")
      (node (ref "U2") (pin "34") (pinfunction "PB13_34") (pintype "bidirectional"))
    )
    (net (code "99") (name "unconnected-(U2A-PB14-Pad35)") (class "Default")
      (node (ref "U2") (pin "35") (pinfunction "PB14_35") (pintype "bidirectional"))
    )
    (net (code "100") (name "unconnected-(U2A-PB15-Pad36)") (class "Default")
      (node (ref "U2") (pin "36") (pinfunction "PB15_36") (pintype "bidirectional"))
    )
    (net (code "101") (name "unconnected-(U2A-PC0-Pad8)") (class "Default")
      (node (ref "U2") (pin "8") (pinfunction "PC0_8") (pintype "bidirectional"))
    )
    (net (code "102") (name "unconnected-(U2A-PC1-Pad9)") (class "Default")
      (node (ref "U2") (pin "9") (pinfunction "PC1_9") (pintype "bidirectional"))
    )
    (net (code "103") (name "unconnected-(U2A-PC2-Pad10)") (class "Default")
      (node (ref "U2") (pin "10") (pinfunction "PC2_10") (pintype "bidirectional"))
    )
    (net (code "104") (name "unconnected-(U2A-PC3-Pad11)") (class "Default")
      (node (ref "U2") (pin "11") (pinfunction "PC3_11") (pintype "bidirectional"))
    )
    (net (code "105") (name "unconnected-(U2A-PC4-Pad24)") (class "Default")
      (node (ref "U2") (pin "24") (pinfunction "PC4_24") (pintype "bidirectional"))
    )
    (net (code "106") (name "unconnected-(U2A-PC8-Pad39)") (class "Default")
      (node (ref "U2") (pin "39") (pinfunction "PC8_39") (pintype "bidirectional"))
    )
    (net (code "107") (name "unconnected-(U2A-PC9-Pad40)") (class "Default")
      (node (ref "U2") (pin "40") (pinfunction "PC9_40") (pintype "bidirectional"))
    )
    (net (code "108") (name "unconnected-(U2A-PC10-Pad51)") (class "Default")
      (node (ref "U2") (pin "51") (pinfunction "PC10_51") (pintype "bidirectional"))
    )
    (net (code "109") (name "unconnected-(U2A-PC11-Pad52)") (class "Default")
      (node (ref "U2") (pin "52") (pinfunction "PC11_52") (pintype "bidirectional"))
    )
    (net (code "110") (name "unconnected-(U2A-PC13-Pad2)") (class "Default")
      (node (ref "U2") (pin "2") (pinfunction "PC13_2") (pintype "bidirectional"))
    )
    (net (code "111") (name "unconnected-(U2A-PC14-OSC32_IN-Pad3)") (class "Default")
      (node (ref "U2") (pin "3") (pinfunction "PC14-OSC32_IN_3") (pintype "bidirectional"))
    )
    (net (code "112") (name "unconnected-(U2A-PC15-OSC32_OUT-Pad4)") (class "Default")
      (node (ref "U2") (pin "4") (pinfunction "PC15-OSC32_OUT_4") (pintype "bidirectional"))
    )
    (net (code "113") (name "unconnected-(U2A-PH0-OSC_IN-Pad5)") (class "Default")
      (node (ref "U2") (pin "5") (pinfunction "PH0-OSC_IN_5") (pintype "bidirectional"))
    )
    (net (code "114") (name "unconnected-(U2A-PH1-Pad6)") (class "Default")
      (node (ref "U2") (pin "6") (pinfunction "PH1_6") (pintype "bidirectional"))
    )
    (net (code "115") (name "unconnected-(U4-INT-Pad6)") (class "Default")
      (node (ref "U4") (pin "6") (pinfunction "INT_6") (pintype "bidirectional"))
    )
    (net (code "116") (name "unconnected-(U4-RST-Pad5)") (class "Default")
      (node (ref "U4") (pin "5") (pinfunction "RST_5") (pintype "bidirectional"))
    )
    (net (code "117") (name "unconnected-(X1-3V3-PadP$12)") (class "Default")
      (node (ref "X1") (pin "P$12") (pinfunction "3V3_P$12") (pintype "bidirectional"))
    )
    (net (code "118") (name "unconnected-(X1-5V-PadP$14)") (class "Default")
      (node (ref "X1") (pin "P$14") (pinfunction "5V_P$14") (pintype "bidirectional"))
    )
    (net (code "119") (name "unconnected-(X1-PA02_A0_D0-PadP$1)") (class "Default")
      (node (ref "X1") (pin "P$1") (pinfunction "PA02_A0_D0_P$1") (pintype "bidirectional"))
    )
    (net (code "120") (name "unconnected-(X1-PA4_A1_D1-PadP$2)") (class "Default")
      (node (ref "X1") (pin "P$2") (pinfunction "PA4_A1_D1_P$2") (pintype "bidirectional"))
    )
    (net (code "121") (name "unconnected-(X1-PA5_A9_D9_MISO-PadP$10)") (class "Default")
      (node (ref "X1") (pin "P$10") (pinfunction "PA5_A9_D9_MISO_P$10") (pintype "bidirectional"))
    )
    (net (code "122") (name "unconnected-(X1-PA6_A10_D10_MOSI-PadP$11)") (class "Default")
      (node (ref "X1") (pin "P$11") (pinfunction "PA6_A10_D10_MOSI_P$11") (pintype "bidirectional"))
    )
    (net (code "123") (name "unconnected-(X1-PA7_A8_D8_SCK-PadP$9)") (class "Default")
      (node (ref "X1") (pin "P$9") (pinfunction "PA7_A8_D8_SCK_P$9") (pintype "bidirectional"))
    )
    (net (code "124") (name "unconnected-(X1-PA8_A4_D4_SDA-PadP$5)") (class "Default")
      (node (ref "X1") (pin "P$5") (pinfunction "PA8_A4_D4_SDA_P$5") (pintype "bidirectional"))
    )
    (net (code "125") (name "unconnected-(X1-PA9_A5_D5_SCL-PadP$6)") (class "Default")
      (node (ref "X1") (pin "P$6") (pinfunction "PA9_A5_D5_SCL_P$6") (pintype "bidirectional"))
    )
    (net (code "126") (name "unconnected-(X1-PA10_A2_D2-PadP$3)") (class "Default")
      (node (ref "X1") (pin "P$3") (pinfunction "PA10_A2_D2_P$3") (pintype "bidirectional"))
    )
    (net (code "127") (name "unconnected-(X1-PA11_A3_D3-PadP$4)") (class "Default")
      (node (ref "X1") (pin "P$4") (pinfunction "PA11_A3_D3_P$4") (pintype "bidirectional"))
    )
    (net (code "128") (name "unconnected-(X2-SBU1-PadA8)") (class "Default")
      (node (ref "X2") (pin "A8") (pinfunction "SBU1_A8") (pintype "bidirectional"))
    )
    (net (code "129") (name "unconnected-(X2-SBU2-PadB8)") (class "Default")
      (node (ref "X2") (pin "B8") (pinfunction "SBU2_B8") (pintype "bidirectional"))
    )
    (net (code "130") (name "unconnected-(X3-SBU1-PadA8)") (class "Default")
      (node (ref "X3") (pin "A8") (pinfunction "SBU1_A8") (pintype "bidirectional"))
    )
    (net (code "131") (name "unconnected-(X3-SBU2-PadB8)") (class "Default")
      (node (ref "X3") (pin "B8") (pinfunction "SBU2_B8") (pintype "bidirectional"))
    )
    (net (code "132") (name "~{RE}") (class "Default")
      (node (ref "Q1") (pin "3") (pinfunction "C_3") (pintype "passive"))
      (node (ref "R14") (pin "1") (pinfunction "1_1") (pintype "passive"))
      (node (ref "U5") (pin "2") (pinfunction "~{RE}_2") (pintype "input"))
      (node (ref "U5") (pin "3") (pinfunction "DE_3") (pintype "input"))
    )
  )
)
